# Mcu.net
KiCad netlist of a schematic drawn in Altium Designer
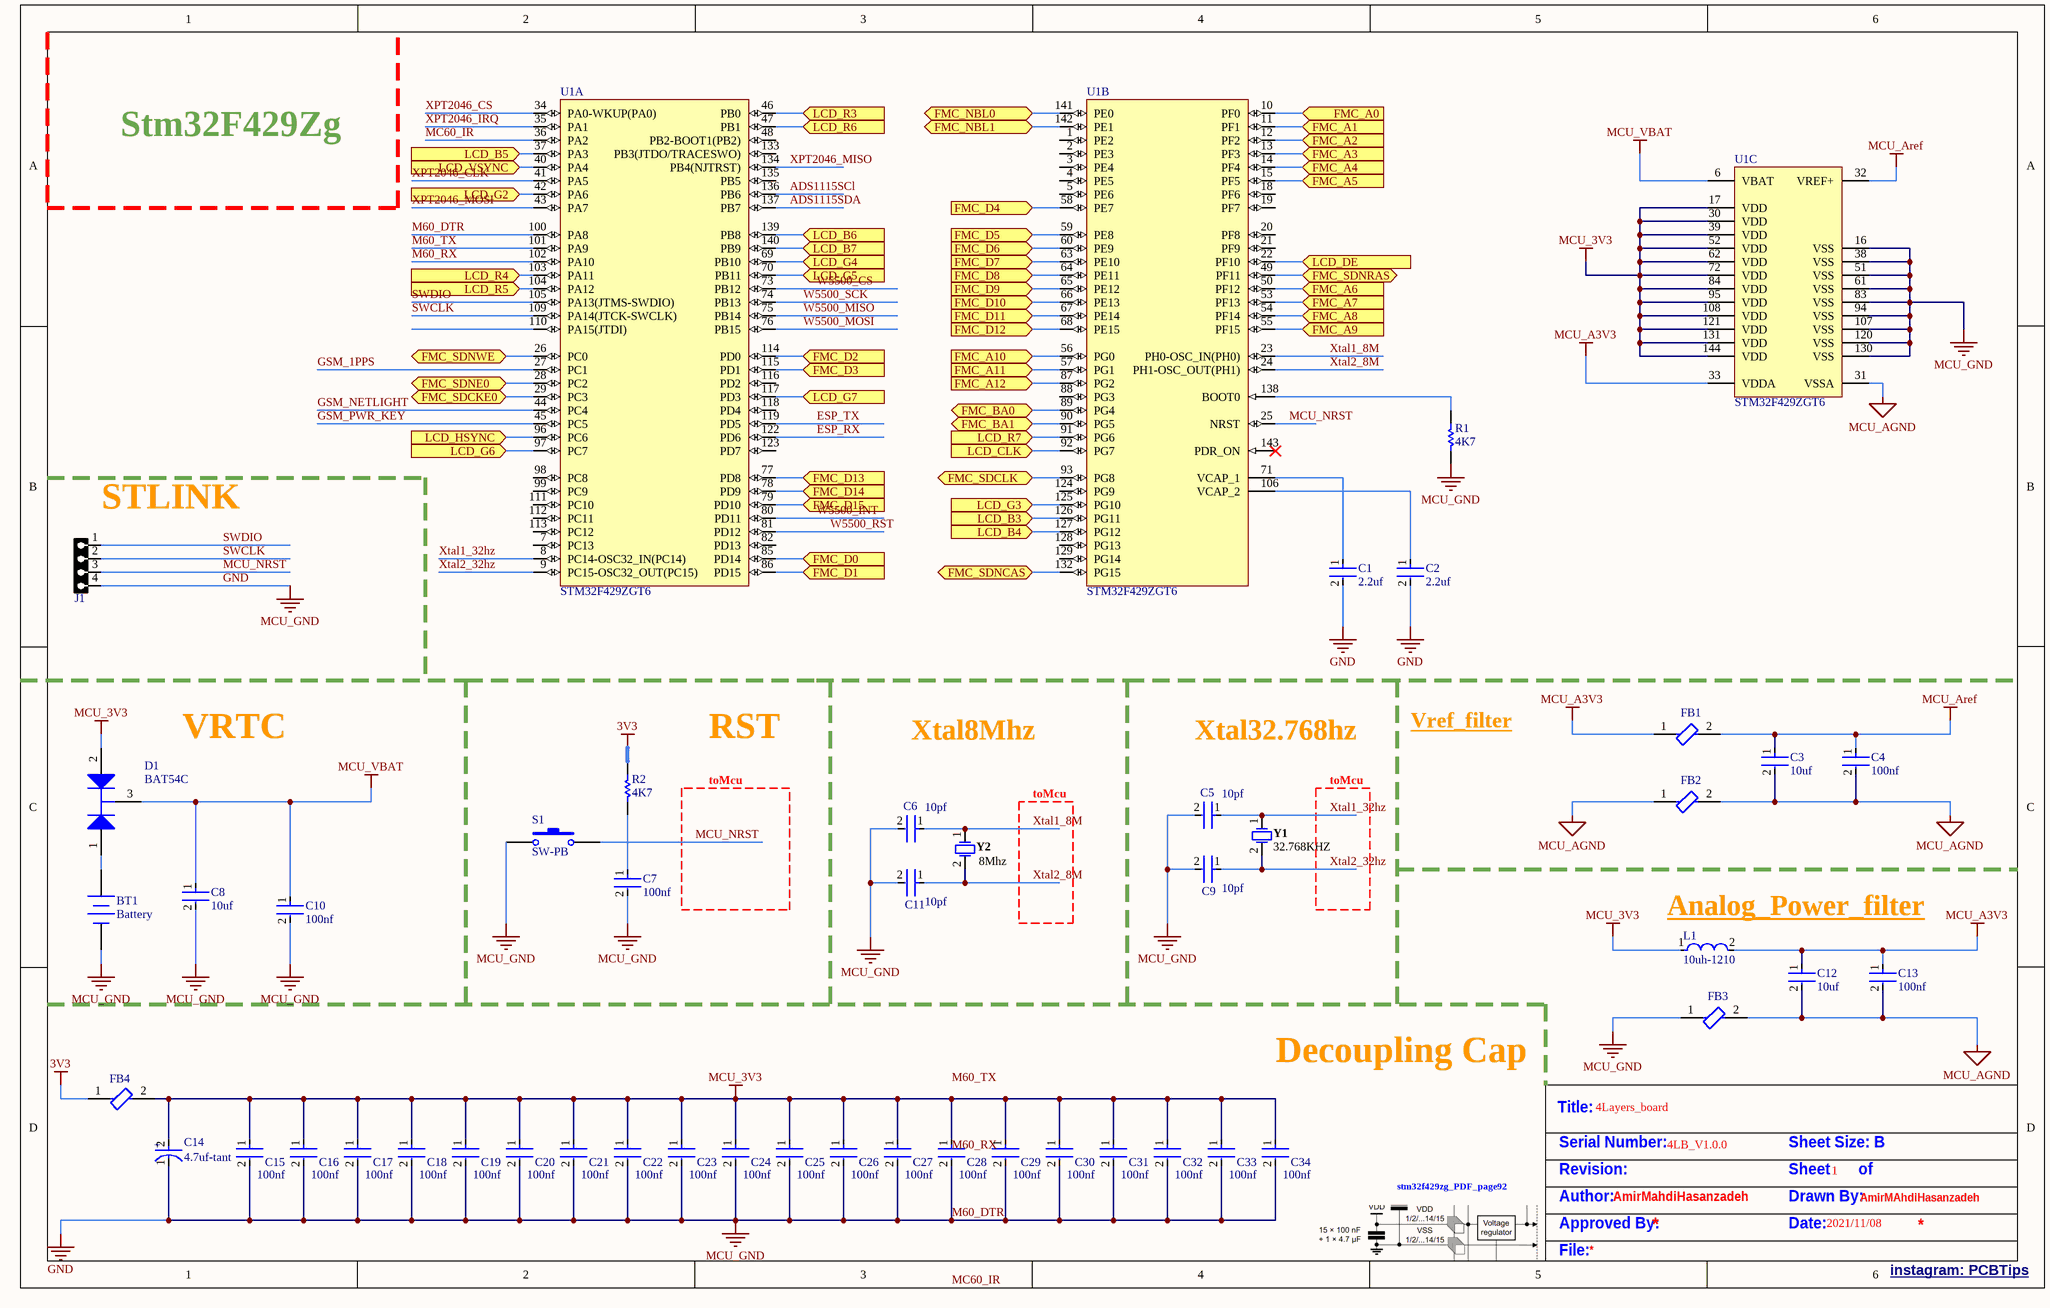
[diagram p0: Mcu.SchDoc]

(export (version "E")
  (design (tool "Eeschema 10.0.6"))
  (components
    (comp (ref "BT1")
      (value "Battery")
      (footprint "BTH1220")
      (description "Multicell Battery")
      (fields (field (name "PUBLISHER") "Altium Limited"))
      (libsource (lib "Miscellaneous Devices") (part "Battery"))
    )
    (comp (ref "C1")
      (value "2.2uf")
      (footprint "FP-C3216-160-0_2-IPC_A")
      (description "Multilayer Ceramic Capacitors 10uF ±10% 50V X5R SMD 1206")
      (fields (field (name "TOLERANCE") "10%") (field (name "VOLTAGE") "50V"))
      (libsource (lib "Altium Content Vault") (part "11868f565c42a9108669ba33697ecf6"))
    )
    (comp (ref "C2")
      (value "2.2uf")
      (footprint "FP-C3216-160-0_2-IPC_A")
      (description "Multilayer Ceramic Capacitors 10uF ±10% 50V X5R SMD 1206")
      (fields (field (name "TOLERANCE") "10%") (field (name "VOLTAGE") "50V"))
      (libsource (lib "Altium Content Vault") (part "11868f565c42a9108669ba33697ecf6"))
    )
    (comp (ref "C3")
      (value "10uf")
      (footprint "FP-C3216-160-0_2-IPC_A")
      (description "Multilayer Ceramic Capacitors 10uF ±10% 50V X5R SMD 1206")
      (fields (field (name "TOLERANCE") "10%") (field (name "VOLTAGE") "50V"))
      (libsource (lib "Altium Content Vault") (part "11868f565c42a9108669ba33697ecf6"))
    )
    (comp (ref "C4")
      (value "100nf")
      (footprint "FP-CGA3E-0_3-0_1-IPC_A")
      (description "Cap Ceramic 100nF 50V X7R 10% Pad SMD 0603 +125°C Automotive T/R")
      (fields (field (name "TOLERANCE") "10%") (field (name "VOLTAGE") "50V"))
      (libsource (lib "Altium Content Vault") (part "b4654b650e69147ec39a6b967a45e02"))
    )
    (comp (ref "C5")
      (value "10pf")
      (footprint "FP-CGA3E-0_3-0_1-IPC_A")
      (description "Cap Ceramic 100nF 50V X7R 10% Pad SMD 0603 +125°C Automotive T/R")
      (fields (field (name "TOLERANCE") "10%") (field (name "VOLTAGE") "50V"))
      (libsource (lib "Altium Content Vault") (part "b4654b650e69147ec39a6b967a45e02"))
    )
    (comp (ref "C6")
      (value "10pf")
      (footprint "FP-CGA3E-0_3-0_1-IPC_A")
      (description "Cap Ceramic 100nF 50V X7R 10% Pad SMD 0603 +125°C Automotive T/R")
      (fields (field (name "TOLERANCE") "10%") (field (name "VOLTAGE") "50V"))
      (libsource (lib "Altium Content Vault") (part "b4654b650e69147ec39a6b967a45e02"))
    )
    (comp (ref "C7")
      (value "100nf")
      (footprint "FP-CGA3E-0_3-0_1-IPC_A")
      (description "Cap Ceramic 100nF 50V X7R 10% Pad SMD 0603 +125°C Automotive T/R")
      (fields (field (name "TOLERANCE") "10%") (field (name "VOLTAGE") "50V"))
      (libsource (lib "Altium Content Vault") (part "b4654b650e69147ec39a6b967a45e02"))
    )
    (comp (ref "C8")
      (value "10uf")
      (footprint "FP-C3216-160-0_2-IPC_A")
      (description "Multilayer Ceramic Capacitors 10uF ±10% 50V X5R SMD 1206")
      (fields (field (name "TOLERANCE") "10%") (field (name "VOLTAGE") "50V"))
      (libsource (lib "Altium Content Vault") (part "11868f565c42a9108669ba33697ecf6"))
    )
    (comp (ref "C9")
      (value "10pf")
      (footprint "FP-CGA3E-0_3-0_1-IPC_A")
      (description "Cap Ceramic 100nF 50V X7R 10% Pad SMD 0603 +125°C Automotive T/R")
      (fields (field (name "TOLERANCE") "10%") (field (name "VOLTAGE") "50V"))
      (libsource (lib "Altium Content Vault") (part "b4654b650e69147ec39a6b967a45e02"))
    )
    (comp (ref "C10")
      (value "100nf")
      (footprint "FP-CGA3E-0_3-0_1-IPC_A")
      (description "Cap Ceramic 100nF 50V X7R 10% Pad SMD 0603 +125°C Automotive T/R")
      (fields (field (name "TOLERANCE") "10%") (field (name "VOLTAGE") "50V"))
      (libsource (lib "Altium Content Vault") (part "b4654b650e69147ec39a6b967a45e02"))
    )
    (comp (ref "C11")
      (value "10pf")
      (footprint "FP-CGA3E-0_3-0_1-IPC_A")
      (description "Cap Ceramic 100nF 50V X7R 10% Pad SMD 0603 +125°C Automotive T/R")
      (fields (field (name "TOLERANCE") "10%") (field (name "VOLTAGE") "50V"))
      (libsource (lib "Altium Content Vault") (part "b4654b650e69147ec39a6b967a45e02"))
    )
    (comp (ref "C12")
      (value "10uf")
      (footprint "FP-C3216-160-0_2-IPC_A")
      (description "Multilayer Ceramic Capacitors 10uF ±10% 50V X5R SMD 1206")
      (fields (field (name "TOLERANCE") "10%") (field (name "VOLTAGE") "50V"))
      (libsource (lib "Altium Content Vault") (part "11868f565c42a9108669ba33697ecf6"))
    )
    (comp (ref "C13")
      (value "100nf")
      (footprint "FP-CGA3E-0_3-0_1-IPC_A")
      (description "Cap Ceramic 100nF 50V X7R 10% Pad SMD 0603 +125°C Automotive T/R")
      (fields (field (name "TOLERANCE") "10%") (field (name "VOLTAGE") "50V"))
      (libsource (lib "Altium Content Vault") (part "b4654b650e69147ec39a6b967a45e02"))
    )
    (comp (ref "C14")
      (value "4.7uf-tant")
      (footprint "FP-T491A475K016AT-MFG")
      (description "CAP TANT 4.7UF 10% 16V 1206")
      (fields (field (name "TOLERANCE") "10%") (field (name "VOLTAGE") "16V"))
      (libsource (lib "Altium Content Vault") (part "cf48714ba7e38822c1575c7ec0b6d1f"))
    )
    (comp (ref "C15")
      (value "100nf")
      (footprint "FP-CGA3E-0_3-0_1-IPC_A")
      (description "Cap Ceramic 100nF 50V X7R 10% Pad SMD 0603 +125°C Automotive T/R")
      (fields (field (name "TOLERANCE") "10%") (field (name "VOLTAGE") "50V"))
      (libsource (lib "Altium Content Vault") (part "b4654b650e69147ec39a6b967a45e02"))
    )
    (comp (ref "C16")
      (value "100nf")
      (footprint "FP-CGA3E-0_3-0_1-IPC_A")
      (description "Cap Ceramic 100nF 50V X7R 10% Pad SMD 0603 +125°C Automotive T/R")
      (fields (field (name "TOLERANCE") "10%") (field (name "VOLTAGE") "50V"))
      (libsource (lib "Altium Content Vault") (part "b4654b650e69147ec39a6b967a45e02"))
    )
    (comp (ref "C17")
      (value "100nf")
      (footprint "FP-CGA3E-0_3-0_1-IPC_A")
      (description "Cap Ceramic 100nF 50V X7R 10% Pad SMD 0603 +125°C Automotive T/R")
      (fields (field (name "TOLERANCE") "10%") (field (name "VOLTAGE") "50V"))
      (libsource (lib "Altium Content Vault") (part "b4654b650e69147ec39a6b967a45e02"))
    )
    (comp (ref "C18")
      (value "100nf")
      (footprint "FP-CGA3E-0_3-0_1-IPC_A")
      (description "Cap Ceramic 100nF 50V X7R 10% Pad SMD 0603 +125°C Automotive T/R")
      (fields (field (name "TOLERANCE") "10%") (field (name "VOLTAGE") "50V"))
      (libsource (lib "Altium Content Vault") (part "b4654b650e69147ec39a6b967a45e02"))
    )
    (comp (ref "C19")
      (value "100nf")
      (footprint "FP-CGA3E-0_3-0_1-IPC_A")
      (description "Cap Ceramic 100nF 50V X7R 10% Pad SMD 0603 +125°C Automotive T/R")
      (fields (field (name "TOLERANCE") "10%") (field (name "VOLTAGE") "50V"))
      (libsource (lib "Altium Content Vault") (part "b4654b650e69147ec39a6b967a45e02"))
    )
    (comp (ref "C20")
      (value "100nf")
      (footprint "FP-CGA3E-0_3-0_1-IPC_A")
      (description "Cap Ceramic 100nF 50V X7R 10% Pad SMD 0603 +125°C Automotive T/R")
      (fields (field (name "TOLERANCE") "10%") (field (name "VOLTAGE") "50V"))
      (libsource (lib "Altium Content Vault") (part "b4654b650e69147ec39a6b967a45e02"))
    )
    (comp (ref "C21")
      (value "100nf")
      (footprint "FP-CGA3E-0_3-0_1-IPC_A")
      (description "Cap Ceramic 100nF 50V X7R 10% Pad SMD 0603 +125°C Automotive T/R")
      (fields (field (name "TOLERANCE") "10%") (field (name "VOLTAGE") "50V"))
      (libsource (lib "Altium Content Vault") (part "b4654b650e69147ec39a6b967a45e02"))
    )
    (comp (ref "C22")
      (value "100nf")
      (footprint "FP-CGA3E-0_3-0_1-IPC_A")
      (description "Cap Ceramic 100nF 50V X7R 10% Pad SMD 0603 +125°C Automotive T/R")
      (fields (field (name "TOLERANCE") "10%") (field (name "VOLTAGE") "50V"))
      (libsource (lib "Altium Content Vault") (part "b4654b650e69147ec39a6b967a45e02"))
    )
    (comp (ref "C23")
      (value "100nf")
      (footprint "FP-CGA3E-0_3-0_1-IPC_A")
      (description "Cap Ceramic 100nF 50V X7R 10% Pad SMD 0603 +125°C Automotive T/R")
      (fields (field (name "TOLERANCE") "10%") (field (name "VOLTAGE") "50V"))
      (libsource (lib "Altium Content Vault") (part "b4654b650e69147ec39a6b967a45e02"))
    )
    (comp (ref "C24")
      (value "100nf")
      (footprint "FP-CGA3E-0_3-0_1-IPC_A")
      (description "Cap Ceramic 100nF 50V X7R 10% Pad SMD 0603 +125°C Automotive T/R")
      (fields (field (name "TOLERANCE") "10%") (field (name "VOLTAGE") "50V"))
      (libsource (lib "Altium Content Vault") (part "b4654b650e69147ec39a6b967a45e02"))
    )
    (comp (ref "C25")
      (value "100nf")
      (footprint "FP-CGA3E-0_3-0_1-IPC_A")
      (description "Cap Ceramic 100nF 50V X7R 10% Pad SMD 0603 +125°C Automotive T/R")
      (fields (field (name "TOLERANCE") "10%") (field (name "VOLTAGE") "50V"))
      (libsource (lib "Altium Content Vault") (part "b4654b650e69147ec39a6b967a45e02"))
    )
    (comp (ref "C26")
      (value "100nf")
      (footprint "FP-CGA3E-0_3-0_1-IPC_A")
      (description "Cap Ceramic 100nF 50V X7R 10% Pad SMD 0603 +125°C Automotive T/R")
      (fields (field (name "TOLERANCE") "10%") (field (name "VOLTAGE") "50V"))
      (libsource (lib "Altium Content Vault") (part "b4654b650e69147ec39a6b967a45e02"))
    )
    (comp (ref "C27")
      (value "100nf")
      (footprint "FP-CGA3E-0_3-0_1-IPC_A")
      (description "Cap Ceramic 100nF 50V X7R 10% Pad SMD 0603 +125°C Automotive T/R")
      (fields (field (name "TOLERANCE") "10%") (field (name "VOLTAGE") "50V"))
      (libsource (lib "Altium Content Vault") (part "b4654b650e69147ec39a6b967a45e02"))
    )
    (comp (ref "C28")
      (value "100nf")
      (footprint "FP-CGA3E-0_3-0_1-IPC_A")
      (description "Cap Ceramic 100nF 50V X7R 10% Pad SMD 0603 +125°C Automotive T/R")
      (fields (field (name "TOLERANCE") "10%") (field (name "VOLTAGE") "50V"))
      (libsource (lib "Altium Content Vault") (part "b4654b650e69147ec39a6b967a45e02"))
    )
    (comp (ref "C29")
      (value "100nf")
      (footprint "FP-CGA3E-0_3-0_1-IPC_A")
      (description "Cap Ceramic 100nF 50V X7R 10% Pad SMD 0603 +125°C Automotive T/R")
      (fields (field (name "TOLERANCE") "10%") (field (name "VOLTAGE") "50V"))
      (libsource (lib "Altium Content Vault") (part "b4654b650e69147ec39a6b967a45e02"))
    )
    (comp (ref "C30")
      (value "100nf")
      (footprint "FP-CGA3E-0_3-0_1-IPC_A")
      (description "Cap Ceramic 100nF 50V X7R 10% Pad SMD 0603 +125°C Automotive T/R")
      (fields (field (name "TOLERANCE") "10%") (field (name "VOLTAGE") "50V"))
      (libsource (lib "Altium Content Vault") (part "b4654b650e69147ec39a6b967a45e02"))
    )
    (comp (ref "C31")
      (value "100nf")
      (footprint "FP-CGA3E-0_3-0_1-IPC_A")
      (description "Cap Ceramic 100nF 50V X7R 10% Pad SMD 0603 +125°C Automotive T/R")
      (fields (field (name "TOLERANCE") "10%") (field (name "VOLTAGE") "50V"))
      (libsource (lib "Altium Content Vault") (part "b4654b650e69147ec39a6b967a45e02"))
    )
    (comp (ref "C32")
      (value "100nf")
      (footprint "FP-CGA3E-0_3-0_1-IPC_A")
      (description "Cap Ceramic 100nF 50V X7R 10% Pad SMD 0603 +125°C Automotive T/R")
      (fields (field (name "TOLERANCE") "10%") (field (name "VOLTAGE") "50V"))
      (libsource (lib "Altium Content Vault") (part "b4654b650e69147ec39a6b967a45e02"))
    )
    (comp (ref "C33")
      (value "100nf")
      (footprint "FP-CGA3E-0_3-0_1-IPC_A")
      (description "Cap Ceramic 100nF 50V X7R 10% Pad SMD 0603 +125°C Automotive T/R")
      (fields (field (name "TOLERANCE") "10%") (field (name "VOLTAGE") "50V"))
      (libsource (lib "Altium Content Vault") (part "b4654b650e69147ec39a6b967a45e02"))
    )
    (comp (ref "C34")
      (value "100nf")
      (footprint "FP-CGA3E-0_3-0_1-IPC_A")
      (description "Cap Ceramic 100nF 50V X7R 10% Pad SMD 0603 +125°C Automotive T/R")
      (fields (field (name "TOLERANCE") "10%") (field (name "VOLTAGE") "50V"))
      (libsource (lib "Altium Content Vault") (part "b4654b650e69147ec39a6b967a45e02"))
    )
    (comp (ref "D1")
      (value "BAT54C")
      (footprint "ONSC-SOT-323-3-419-04_V")
      (description "Dual Series Cathode Schottky Barrier Diodes, 3-Pin SOT-323, Pb-Free, Tape and Reel")
      (fields (field (name "MANUFACTURER") "On Semiconductor") (field (name "PARTNUMBER") "SBAT54CWT1G"))
      (libsource (lib "Altium Content Vault") (part "ONSC-D-A1A2K3-3"))
    )
    (comp (ref "FB1")
      (value "MMZ1608R600ATA00")
      (footprint "FP-MMZ1608-0_8-MFG")
      (description "Signal Line Ferrite Bead 60Ω  @ 100MHz 800mA DCR 100mΩ SMD 0603")
      (fields (field (name "TOLERANCE") "25%"))
      (libsource (lib "Altium Content Vault") (part "5f30dd21d616792df468990f7003faa"))
    )
    (comp (ref "FB2")
      (value "MMZ1608R600ATA00")
      (footprint "FP-MMZ1608-0_8-MFG")
      (description "Signal Line Ferrite Bead 60Ω  @ 100MHz 800mA DCR 100mΩ SMD 0603")
      (fields (field (name "TOLERANCE") "25%"))
      (libsource (lib "Altium Content Vault") (part "5f30dd21d616792df468990f7003faa"))
    )
    (comp (ref "FB3")
      (value "MMZ1608R600ATA00")
      (footprint "FP-MMZ1608-0_8-MFG")
      (description "Signal Line Ferrite Bead 60Ω  @ 100MHz 800mA DCR 100mΩ SMD 0603")
      (fields (field (name "TOLERANCE") "25%"))
      (libsource (lib "Altium Content Vault") (part "5f30dd21d616792df468990f7003faa"))
    )
    (comp (ref "FB4")
      (value "MMZ1608R600ATA00")
      (footprint "FP-MMZ1608-0_8-MFG")
      (description "Signal Line Ferrite Bead 60Ω  @ 100MHz 800mA DCR 100mΩ SMD 0603")
      (fields (field (name "TOLERANCE") "25%"))
      (libsource (lib "Altium Content Vault") (part "5f30dd21d616792df468990f7003faa"))
    )
    (comp (ref "J1")
      (value "HDRF4")
      (footprint "HDR_F_1X4")
      (description "CONN, HEADER, Female, pitch: 2.54mm, 4POS")
      (libsource (lib "conn_header_2.54_st") (part "HDR_F_1X4"))
    )
    (comp (ref "L1")
      (value "10uh-1210")
      (footprint "FP-CB3225-IPC_A")
      (description "SMD Inductors 10uH ±20% 0.9A 0.1729Ω 1210")
      (fields (field (name "TOLERANCE") "20%"))
      (libsource (lib "Altium Content Vault") (part "725321dda6339637d4d059423bc1c3c"))
    )
    (comp (ref "R1")
      (value "4K7")
      (footprint "RESC1608X55X25ML10T15")
      (description "Chip Resistor, 0 Ohm, +/- 5%, 0.1 W, -55 to 155 degC, 0603 (1608 Metric), RoHS, Tape and Reel")
      (fields (field (name "TOLERANCE") "5%") (field (name "MANUFACTURER") "Yageo"))
      (libsource (lib "Altium Content Vault") (part "RES-2"))
    )
    (comp (ref "R2")
      (value "4K7")
      (footprint "RESC1608X55X25ML10T15")
      (description "Chip Resistor, 0 Ohm, +/- 5%, 0.1 W, -55 to 155 degC, 0603 (1608 Metric), RoHS, Tape and Reel")
      (fields (field (name "TOLERANCE") "5%") (field (name "MANUFACTURER") "Yageo"))
      (libsource (lib "Altium Content Vault") (part "RES-2"))
    )
    (comp (ref "S1")
      (value "SW-PB")
      (footprint "SWPBS_SPST_6X3X5")
      (description "Switch")
      (fields (field (name "PUBLISHER") "Altium Limited"))
      (libsource (lib "Miscellaneous Devices") (part "SW-PB"))
    )
    (comp (ref "U1")
      (value "STM32F429ZGT6")
      (footprint "STM-LQFP144_V")
      (fields (field (name "MANUFACTURER") "STMicroelectronics"))
      (libsource (lib "Altium Content Vault") (part "MC-ARM-STM32F4X9-SQ144"))
    )
    (comp (ref "Y1")
      (value "32.768KHZ")
      (footprint "ABRA-AB26T")
      (description "Crystal, 12.5 pF, 32.768 KHz, -10 to 60 degC, 2-Pin THD, RoHS, Bulk")
      (fields (field (name "MANUFACTURER") "ABRACON") (field (name "TOLERANCE") "20PPM"))
      (libsource (lib "Altium Content Vault") (part "XTAL-1-2-2"))
    )
    (comp (ref "Y2")
      (value "8Mhz")
      (footprint "FOX-HC49SDLF_V")
      (description "Resistance Weld Crystal, 8 MHz, +/- 30 ppm, -20 to 70 degC, 2-Pin SMD, RoHS, Tape and Reel")
      (fields (field (name "MANUFACTURER") "FOX Electronics") (field (name "TOLERANCE") "50ppm"))
      (libsource (lib "Altium Content Vault") (part "XTAL-1-2-2"))
    )
  )
  (nets
    (net (code "1") (name "/ADS1115SCl") (class "Default")
      (node (ref "U1") (pin "136") (pinfunction "PB6_136") (pintype "bidirectional"))
    )
    (net (code "2") (name "/ADS1115SDA") (class "Default")
      (node (ref "U1") (pin "137") (pinfunction "PB7_137") (pintype "bidirectional"))
    )
    (net (code "3") (name "/ESP_RX") (class "Default")
      (node (ref "U1") (pin "122") (pinfunction "PD6_122") (pintype "bidirectional"))
    )
    (net (code "4") (name "/ESP_TX") (class "Default")
      (node (ref "U1") (pin "119") (pinfunction "PD5_119") (pintype "bidirectional"))
    )
    (net (code "5") (name "/FMC_A0") (class "Default")
      (node (ref "U1") (pin "10") (pinfunction "PF0_10") (pintype "bidirectional"))
    )
    (net (code "6") (name "/FMC_A1") (class "Default")
      (node (ref "U1") (pin "11") (pinfunction "PF1_11") (pintype "bidirectional"))
    )
    (net (code "7") (name "/FMC_A2") (class "Default")
      (node (ref "U1") (pin "12") (pinfunction "PF2_12") (pintype "bidirectional"))
    )
    (net (code "8") (name "/FMC_A3") (class "Default")
      (node (ref "U1") (pin "13") (pinfunction "PF3_13") (pintype "bidirectional"))
    )
    (net (code "9") (name "/FMC_A4") (class "Default")
      (node (ref "U1") (pin "14") (pinfunction "PF4_14") (pintype "bidirectional"))
    )
    (net (code "10") (name "/FMC_A5") (class "Default")
      (node (ref "U1") (pin "15") (pinfunction "PF5_15") (pintype "bidirectional"))
    )
    (net (code "11") (name "/FMC_A6") (class "Default")
      (node (ref "U1") (pin "50") (pinfunction "PF12_50") (pintype "bidirectional"))
    )
    (net (code "12") (name "/FMC_A7") (class "Default")
      (node (ref "U1") (pin "53") (pinfunction "PF13_53") (pintype "bidirectional"))
    )
    (net (code "13") (name "/FMC_A8") (class "Default")
      (node (ref "U1") (pin "54") (pinfunction "PF14_54") (pintype "bidirectional"))
    )
    (net (code "14") (name "/FMC_A9") (class "Default")
      (node (ref "U1") (pin "55") (pinfunction "PF15_55") (pintype "bidirectional"))
    )
    (net (code "15") (name "/FMC_A10") (class "Default")
      (node (ref "U1") (pin "56") (pinfunction "PG0_56") (pintype "bidirectional"))
    )
    (net (code "16") (name "/FMC_A11") (class "Default")
      (node (ref "U1") (pin "57") (pinfunction "PG1_57") (pintype "bidirectional"))
    )
    (net (code "17") (name "/FMC_A12") (class "Default")
      (node (ref "U1") (pin "87") (pinfunction "PG2_87") (pintype "bidirectional"))
    )
    (net (code "18") (name "/FMC_BA0") (class "Default")
      (node (ref "U1") (pin "89") (pinfunction "PG4_89") (pintype "bidirectional"))
    )
    (net (code "19") (name "/FMC_BA1") (class "Default")
      (node (ref "U1") (pin "90") (pinfunction "PG5_90") (pintype "bidirectional"))
    )
    (net (code "20") (name "/FMC_D0") (class "Default")
      (node (ref "U1") (pin "85") (pinfunction "PD14_85") (pintype "bidirectional"))
    )
    (net (code "21") (name "/FMC_D1") (class "Default")
      (node (ref "U1") (pin "86") (pinfunction "PD15_86") (pintype "bidirectional"))
    )
    (net (code "22") (name "/FMC_D2") (class "Default")
      (node (ref "U1") (pin "114") (pinfunction "PD0_114") (pintype "bidirectional"))
    )
    (net (code "23") (name "/FMC_D3") (class "Default")
      (node (ref "U1") (pin "115") (pinfunction "PD1_115") (pintype "bidirectional"))
    )
    (net (code "24") (name "/FMC_D4") (class "Default")
      (node (ref "U1") (pin "58") (pinfunction "PE7_58") (pintype "bidirectional"))
    )
    (net (code "25") (name "/FMC_D5") (class "Default")
      (node (ref "U1") (pin "59") (pinfunction "PE8_59") (pintype "bidirectional"))
    )
    (net (code "26") (name "/FMC_D6") (class "Default")
      (node (ref "U1") (pin "60") (pinfunction "PE9_60") (pintype "bidirectional"))
    )
    (net (code "27") (name "/FMC_D7") (class "Default")
      (node (ref "U1") (pin "63") (pinfunction "PE10_63") (pintype "bidirectional"))
    )
    (net (code "28") (name "/FMC_D8") (class "Default")
      (node (ref "U1") (pin "64") (pinfunction "PE11_64") (pintype "bidirectional"))
    )
    (net (code "29") (name "/FMC_D9") (class "Default")
      (node (ref "U1") (pin "65") (pinfunction "PE12_65") (pintype "bidirectional"))
    )
    (net (code "30") (name "/FMC_D10") (class "Default")
      (node (ref "U1") (pin "66") (pinfunction "PE13_66") (pintype "bidirectional"))
    )
    (net (code "31") (name "/FMC_D11") (class "Default")
      (node (ref "U1") (pin "67") (pinfunction "PE14_67") (pintype "bidirectional"))
    )
    (net (code "32") (name "/FMC_D12") (class "Default")
      (node (ref "U1") (pin "68") (pinfunction "PE15_68") (pintype "bidirectional"))
    )
    (net (code "33") (name "/FMC_D13") (class "Default")
      (node (ref "U1") (pin "77") (pinfunction "PD8_77") (pintype "bidirectional"))
    )
    (net (code "34") (name "/FMC_D14") (class "Default")
      (node (ref "U1") (pin "78") (pinfunction "PD9_78") (pintype "bidirectional"))
    )
    (net (code "35") (name "/FMC_D15") (class "Default")
      (node (ref "U1") (pin "79") (pinfunction "PD10_79") (pintype "bidirectional"))
    )
    (net (code "36") (name "/FMC_NBL0") (class "Default")
      (node (ref "U1") (pin "141") (pinfunction "PE0_141") (pintype "bidirectional"))
    )
    (net (code "37") (name "/FMC_NBL1") (class "Default")
      (node (ref "U1") (pin "142") (pinfunction "PE1_142") (pintype "bidirectional"))
    )
    (net (code "38") (name "/FMC_SDCKE0") (class "Default")
      (node (ref "U1") (pin "29") (pinfunction "PC3_29") (pintype "bidirectional"))
    )
    (net (code "39") (name "/FMC_SDCLK") (class "Default")
      (node (ref "U1") (pin "93") (pinfunction "PG8_93") (pintype "bidirectional"))
    )
    (net (code "40") (name "/FMC_SDNCAS") (class "Default")
      (node (ref "U1") (pin "132") (pinfunction "PG15_132") (pintype "bidirectional"))
    )
    (net (code "41") (name "/FMC_SDNE0") (class "Default")
      (node (ref "U1") (pin "28") (pinfunction "PC2_28") (pintype "bidirectional"))
    )
    (net (code "42") (name "/FMC_SDNRAS") (class "Default")
      (node (ref "U1") (pin "49") (pinfunction "PF11_49") (pintype "bidirectional"))
    )
    (net (code "43") (name "/FMC_SDNWE") (class "Default")
      (node (ref "U1") (pin "26") (pinfunction "PC0_26") (pintype "bidirectional"))
    )
    (net (code "44") (name "/GSM_1PPS") (class "Default")
      (node (ref "U1") (pin "27") (pinfunction "PC1_27") (pintype "bidirectional"))
    )
    (net (code "45") (name "/GSM_NETLIGHT") (class "Default")
      (node (ref "U1") (pin "44") (pinfunction "PC4_44") (pintype "bidirectional"))
    )
    (net (code "46") (name "/GSM_PWR_KEY") (class "Default")
      (node (ref "U1") (pin "45") (pinfunction "PC5_45") (pintype "bidirectional"))
    )
    (net (code "47") (name "/LCD_B3") (class "Default")
      (node (ref "U1") (pin "126") (pinfunction "PG11_126") (pintype "bidirectional"))
    )
    (net (code "48") (name "/LCD_B4") (class "Default")
      (node (ref "U1") (pin "127") (pinfunction "PG12_127") (pintype "bidirectional"))
    )
    (net (code "49") (name "/LCD_B5") (class "Default")
      (node (ref "U1") (pin "37") (pinfunction "PA3_37") (pintype "bidirectional"))
    )
    (net (code "50") (name "/LCD_B6") (class "Default")
      (node (ref "U1") (pin "139") (pinfunction "PB8_139") (pintype "bidirectional"))
    )
    (net (code "51") (name "/LCD_B7") (class "Default")
      (node (ref "U1") (pin "140") (pinfunction "PB9_140") (pintype "bidirectional"))
    )
    (net (code "52") (name "/LCD_CLK") (class "Default")
      (node (ref "U1") (pin "92") (pinfunction "PG7_92") (pintype "bidirectional"))
    )
    (net (code "53") (name "/LCD_DE") (class "Default")
      (node (ref "U1") (pin "22") (pinfunction "PF10_22") (pintype "bidirectional"))
    )
    (net (code "54") (name "/LCD_G2") (class "Default")
      (node (ref "U1") (pin "42") (pinfunction "PA6_42") (pintype "bidirectional"))
    )
    (net (code "55") (name "/LCD_G3") (class "Default")
      (node (ref "U1") (pin "125") (pinfunction "PG10_125") (pintype "bidirectional"))
    )
    (net (code "56") (name "/LCD_G4") (class "Default")
      (node (ref "U1") (pin "69") (pinfunction "PB10_69") (pintype "bidirectional"))
    )
    (net (code "57") (name "/LCD_G5") (class "Default")
      (node (ref "U1") (pin "70") (pinfunction "PB11_70") (pintype "bidirectional"))
    )
    (net (code "58") (name "/LCD_G6") (class "Default")
      (node (ref "U1") (pin "97") (pinfunction "PC7_97") (pintype "bidirectional"))
    )
    (net (code "59") (name "/LCD_G7") (class "Default")
      (node (ref "U1") (pin "117") (pinfunction "PD3_117") (pintype "bidirectional"))
    )
    (net (code "60") (name "/LCD_HSYNC") (class "Default")
      (node (ref "U1") (pin "96") (pinfunction "PC6_96") (pintype "bidirectional"))
    )
    (net (code "61") (name "/LCD_R3") (class "Default")
      (node (ref "U1") (pin "46") (pinfunction "PB0_46") (pintype "bidirectional"))
    )
    (net (code "62") (name "/LCD_R4") (class "Default")
      (node (ref "U1") (pin "103") (pinfunction "PA11_103") (pintype "bidirectional"))
    )
    (net (code "63") (name "/LCD_R5") (class "Default")
      (node (ref "U1") (pin "104") (pinfunction "PA12_104") (pintype "bidirectional"))
    )
    (net (code "64") (name "/LCD_R6") (class "Default")
      (node (ref "U1") (pin "47") (pinfunction "PB1_47") (pintype "bidirectional"))
    )
    (net (code "65") (name "/LCD_R7") (class "Default")
      (node (ref "U1") (pin "91") (pinfunction "PG6_91") (pintype "bidirectional"))
    )
    (net (code "66") (name "/LCD_VSYNC") (class "Default")
      (node (ref "U1") (pin "40") (pinfunction "PA4_40") (pintype "bidirectional"))
    )
    (net (code "67") (name "/M60_RX") (class "Default")
      (node (ref "U1") (pin "102") (pinfunction "PA10_102") (pintype "bidirectional"))
    )
    (net (code "68") (name "/M60_TX") (class "Default")
      (node (ref "U1") (pin "101") (pinfunction "PA9_101") (pintype "bidirectional"))
    )
    (net (code "69") (name "/MC60_IR") (class "Default")
      (node (ref "U1") (pin "36") (pinfunction "PA2_36") (pintype "bidirectional"))
    )
    (net (code "70") (name "/MCU_NRST") (class "Default")
      (node (ref "J1") (pin "3") (pinfunction "3_3") (pintype "passive"))
      (node (ref "S1") (pin "1") (pinfunction "1_1") (pintype "passive"))
      (node (ref "U1") (pin "25") (pinfunction "NRST_25") (pintype "bidirectional"))
    )
    (net (code "71") (name "/SWCLK") (class "Default")
      (node (ref "J1") (pin "2") (pinfunction "2_2") (pintype "passive"))
      (node (ref "U1") (pin "109") (pinfunction "PA14(JTCK-SWCLK)_109") (pintype "bidirectional"))
    )
    (net (code "72") (name "/SWDIO") (class "Default")
      (node (ref "J1") (pin "1") (pinfunction "1_1") (pintype "passive"))
      (node (ref "U1") (pin "105") (pinfunction "PA13(JTMS-SWDIO)_105") (pintype "bidirectional"))
    )
    (net (code "73") (name "/W5500_CS") (class "Default")
      (node (ref "U1") (pin "73") (pinfunction "PB12_73") (pintype "bidirectional"))
    )
    (net (code "74") (name "/W5500_INT") (class "Default")
      (node (ref "U1") (pin "80") (pinfunction "PD11_80") (pintype "bidirectional"))
    )
    (net (code "75") (name "/W5500_MISO") (class "Default")
      (node (ref "U1") (pin "75") (pinfunction "PB14_75") (pintype "bidirectional"))
    )
    (net (code "76") (name "/W5500_MOSI") (class "Default")
      (node (ref "U1") (pin "76") (pinfunction "PB15_76") (pintype "bidirectional"))
    )
    (net (code "77") (name "/W5500_RST") (class "Default")
      (node (ref "U1") (pin "81") (pinfunction "PD12_81") (pintype "bidirectional"))
    )
    (net (code "78") (name "/W5500_SCK") (class "Default")
      (node (ref "U1") (pin "74") (pinfunction "PB13_74") (pintype "bidirectional"))
    )
    (net (code "79") (name "/XPT2046_CLK") (class "Default")
      (node (ref "U1") (pin "41") (pinfunction "PA5_41") (pintype "bidirectional"))
    )
    (net (code "80") (name "/XPT2046_CS") (class "Default")
      (node (ref "U1") (pin "34") (pinfunction "PA0-WKUP(PA0)_34") (pintype "bidirectional"))
    )
    (net (code "81") (name "/XPT2046_IRQ") (class "Default")
      (node (ref "U1") (pin "35") (pinfunction "PA1_35") (pintype "bidirectional"))
    )
    (net (code "82") (name "/XPT2046_MISO") (class "Default")
      (node (ref "U1") (pin "134") (pinfunction "PB4(NJTRST)_134") (pintype "bidirectional"))
    )
    (net (code "83") (name "/XPT2046_MOSI") (class "Default")
      (node (ref "U1") (pin "43") (pinfunction "PA7_43") (pintype "bidirectional"))
    )
    (net (code "84") (name "/Xtal1_8M") (class "Default")
      (node (ref "C6") (pin "1") (pinfunction "1_1") (pintype "passive"))
      (node (ref "U1") (pin "23") (pinfunction "PH0-OSC_IN(PH0)_23") (pintype "bidirectional"))
      (node (ref "Y2") (pin "1") (pinfunction "1_1") (pintype "passive"))
    )
    (net (code "85") (name "/Xtal1_32hz") (class "Default")
      (node (ref "C5") (pin "1") (pinfunction "1_1") (pintype "passive"))
      (node (ref "U1") (pin "8") (pinfunction "PC14-OSC32_IN(PC14)_8") (pintype "bidirectional"))
      (node (ref "Y1") (pin "1") (pinfunction "1_1") (pintype "passive"))
    )
    (net (code "86") (name "/Xtal2_8M") (class "Default")
      (node (ref "C11") (pin "1") (pinfunction "1_1") (pintype "passive"))
      (node (ref "U1") (pin "24") (pinfunction "PH1-OSC_OUT(PH1)_24") (pintype "bidirectional"))
      (node (ref "Y2") (pin "2") (pinfunction "2_2") (pintype "passive"))
    )
    (net (code "87") (name "/Xtal2_32hz") (class "Default")
      (node (ref "C9") (pin "1") (pinfunction "1_1") (pintype "passive"))
      (node (ref "U1") (pin "9") (pinfunction "PC15-OSC32_OUT(PC15)_9") (pintype "bidirectional"))
      (node (ref "Y1") (pin "2") (pinfunction "2_2") (pintype "passive"))
    )
    (net (code "88") (name "3V3") (class "Default")
      (node (ref "FB4") (pin "1") (pinfunction "1_1") (pintype "passive"))
      (node (ref "R2") (pin "2") (pinfunction "2_2") (pintype "passive"))
    )
    (net (code "89") (name "GND") (class "Default")
      (node (ref "BT1") (pin "2") (pinfunction "-_2") (pintype "passive"))
      (node (ref "C1") (pin "2") (pinfunction "2_2") (pintype "passive"))
      (node (ref "C10") (pin "2") (pinfunction "2_2") (pintype "passive"))
      (node (ref "C11") (pin "2") (pinfunction "2_2") (pintype "passive"))
      (node (ref "C14") (pin "1") (pinfunction "C_1") (pintype "passive"))
      (node (ref "C15") (pin "2") (pinfunction "2_2") (pintype "passive"))
      (node (ref "C16") (pin "2") (pinfunction "2_2") (pintype "passive"))
      (node (ref "C17") (pin "2") (pinfunction "2_2") (pintype "passive"))
      (node (ref "C18") (pin "2") (pinfunction "2_2") (pintype "passive"))
      (node (ref "C19") (pin "2") (pinfunction "2_2") (pintype "passive"))
      (node (ref "C2") (pin "2") (pinfunction "2_2") (pintype "passive"))
      (node (ref "C20") (pin "2") (pinfunction "2_2") (pintype "passive"))
      (node (ref "C21") (pin "2") (pinfunction "2_2") (pintype "passive"))
      (node (ref "C22") (pin "2") (pinfunction "2_2") (pintype "passive"))
      (node (ref "C23") (pin "2") (pinfunction "2_2") (pintype "passive"))
      (node (ref "C24") (pin "2") (pinfunction "2_2") (pintype "passive"))
      (node (ref "C25") (pin "2") (pinfunction "2_2") (pintype "passive"))
      (node (ref "C26") (pin "2") (pinfunction "2_2") (pintype "passive"))
      (node (ref "C27") (pin "2") (pinfunction "2_2") (pintype "passive"))
      (node (ref "C28") (pin "2") (pinfunction "2_2") (pintype "passive"))
      (node (ref "C29") (pin "2") (pinfunction "2_2") (pintype "passive"))
      (node (ref "C30") (pin "2") (pinfunction "2_2") (pintype "passive"))
      (node (ref "C31") (pin "2") (pinfunction "2_2") (pintype "passive"))
      (node (ref "C32") (pin "2") (pinfunction "2_2") (pintype "passive"))
      (node (ref "C33") (pin "2") (pinfunction "2_2") (pintype "passive"))
      (node (ref "C34") (pin "2") (pinfunction "2_2") (pintype "passive"))
      (node (ref "C5") (pin "2") (pinfunction "2_2") (pintype "passive"))
      (node (ref "C6") (pin "2") (pinfunction "2_2") (pintype "passive"))
      (node (ref "C7") (pin "2") (pinfunction "2_2") (pintype "passive"))
      (node (ref "C8") (pin "2") (pinfunction "2_2") (pintype "passive"))
      (node (ref "C9") (pin "2") (pinfunction "2_2") (pintype "passive"))
      (node (ref "FB3") (pin "1") (pinfunction "1_1") (pintype "passive"))
      (node (ref "J1") (pin "4") (pinfunction "4_4") (pintype "passive"))
      (node (ref "R1") (pin "1") (pinfunction "1_1") (pintype "passive"))
      (node (ref "S1") (pin "2") (pinfunction "2_2") (pintype "passive"))
      (node (ref "U1") (pin "100") (pinfunction "PA8_100") (pintype "bidirectional"))
      (node (ref "U1") (pin "107") (pinfunction "VSS_107") (pintype "power_in"))
      (node (ref "U1") (pin "120") (pinfunction "VSS_120") (pintype "power_in"))
      (node (ref "U1") (pin "130") (pinfunction "VSS_130") (pintype "power_in"))
      (node (ref "U1") (pin "16") (pinfunction "VSS_16") (pintype "power_in"))
      (node (ref "U1") (pin "38") (pinfunction "VSS_38") (pintype "power_in"))
      (node (ref "U1") (pin "51") (pinfunction "VSS_51") (pintype "power_in"))
      (node (ref "U1") (pin "61") (pinfunction "VSS_61") (pintype "power_in"))
      (node (ref "U1") (pin "83") (pinfunction "VSS_83") (pintype "power_in"))
      (node (ref "U1") (pin "94") (pinfunction "VSS_94") (pintype "power_in"))
    )
    (net (code "90") (name "MCU_3V3") (class "Default")
      (node (ref "C14") (pin "2") (pinfunction "A_2") (pintype "passive"))
      (node (ref "C15") (pin "1") (pinfunction "1_1") (pintype "passive"))
      (node (ref "C16") (pin "1") (pinfunction "1_1") (pintype "passive"))
      (node (ref "C17") (pin "1") (pinfunction "1_1") (pintype "passive"))
      (node (ref "C18") (pin "1") (pinfunction "1_1") (pintype "passive"))
      (node (ref "C19") (pin "1") (pinfunction "1_1") (pintype "passive"))
      (node (ref "C20") (pin "1") (pinfunction "1_1") (pintype "passive"))
      (node (ref "C21") (pin "1") (pinfunction "1_1") (pintype "passive"))
      (node (ref "C22") (pin "1") (pinfunction "1_1") (pintype "passive"))
      (node (ref "C23") (pin "1") (pinfunction "1_1") (pintype "passive"))
      (node (ref "C24") (pin "1") (pinfunction "1_1") (pintype "passive"))
      (node (ref "C25") (pin "1") (pinfunction "1_1") (pintype "passive"))
      (node (ref "C26") (pin "1") (pinfunction "1_1") (pintype "passive"))
      (node (ref "C27") (pin "1") (pinfunction "1_1") (pintype "passive"))
      (node (ref "C28") (pin "1") (pinfunction "1_1") (pintype "passive"))
      (node (ref "C29") (pin "1") (pinfunction "1_1") (pintype "passive"))
      (node (ref "C30") (pin "1") (pinfunction "1_1") (pintype "passive"))
      (node (ref "C31") (pin "1") (pinfunction "1_1") (pintype "passive"))
      (node (ref "C32") (pin "1") (pinfunction "1_1") (pintype "passive"))
      (node (ref "C33") (pin "1") (pinfunction "1_1") (pintype "passive"))
      (node (ref "C34") (pin "1") (pinfunction "1_1") (pintype "passive"))
      (node (ref "D1") (pin "2") (pinfunction "A2_2") (pintype "passive"))
      (node (ref "FB4") (pin "2") (pinfunction "2_2") (pintype "passive"))
      (node (ref "L1") (pin "1") (pinfunction "1_1") (pintype "passive"))
      (node (ref "U1") (pin "108") (pinfunction "VDD_108") (pintype "power_in"))
      (node (ref "U1") (pin "121") (pinfunction "VDD_121") (pintype "power_in"))
      (node (ref "U1") (pin "131") (pinfunction "VDD_131") (pintype "power_in"))
      (node (ref "U1") (pin "144") (pinfunction "VDD_144") (pintype "power_in"))
      (node (ref "U1") (pin "17") (pinfunction "VDD_17") (pintype "power_in"))
      (node (ref "U1") (pin "30") (pinfunction "VDD_30") (pintype "power_in"))
      (node (ref "U1") (pin "39") (pinfunction "VDD_39") (pintype "power_in"))
      (node (ref "U1") (pin "52") (pinfunction "VDD_52") (pintype "power_in"))
      (node (ref "U1") (pin "62") (pinfunction "VDD_62") (pintype "power_in"))
      (node (ref "U1") (pin "72") (pinfunction "VDD_72") (pintype "power_in"))
      (node (ref "U1") (pin "84") (pinfunction "VDD_84") (pintype "power_in"))
      (node (ref "U1") (pin "95") (pinfunction "VDD_95") (pintype "power_in"))
    )
    (net (code "91") (name "MCU_A3V3") (class "Default")
      (node (ref "C12") (pin "1") (pinfunction "1_1") (pintype "passive"))
      (node (ref "C13") (pin "1") (pinfunction "1_1") (pintype "passive"))
      (node (ref "FB1") (pin "1") (pinfunction "1_1") (pintype "passive"))
      (node (ref "L1") (pin "2") (pinfunction "2_2") (pintype "passive"))
      (node (ref "U1") (pin "33") (pinfunction "VDDA_33") (pintype "power_in"))
    )
    (net (code "92") (name "MCU_AGND") (class "Default")
      (node (ref "C12") (pin "2") (pinfunction "2_2") (pintype "passive"))
      (node (ref "C13") (pin "2") (pinfunction "2_2") (pintype "passive"))
      (node (ref "C3") (pin "2") (pinfunction "2_2") (pintype "passive"))
      (node (ref "C4") (pin "2") (pinfunction "2_2") (pintype "passive"))
      (node (ref "FB2") (pin "1") (pinfunction "1_1") (pintype "passive"))
      (node (ref "FB2") (pin "2") (pinfunction "2_2") (pintype "passive"))
      (node (ref "FB3") (pin "2") (pinfunction "2_2") (pintype "passive"))
      (node (ref "U1") (pin "31") (pinfunction "VSSA_31") (pintype "power_in"))
    )
    (net (code "93") (name "MCU_Aref") (class "Default")
      (node (ref "C3") (pin "1") (pinfunction "1_1") (pintype "passive"))
      (node (ref "C4") (pin "1") (pinfunction "1_1") (pintype "passive"))
      (node (ref "FB1") (pin "2") (pinfunction "2_2") (pintype "passive"))
      (node (ref "U1") (pin "32") (pinfunction "VREF+_32") (pintype "power_in"))
    )
    (net (code "94") (name "MCU_VBAT") (class "Default")
      (node (ref "C10") (pin "1") (pinfunction "1_1") (pintype "passive"))
      (node (ref "C8") (pin "1") (pinfunction "1_1") (pintype "passive"))
      (node (ref "D1") (pin "3") (pinfunction "K_3") (pintype "passive"))
      (node (ref "U1") (pin "6") (pinfunction "VBAT_6") (pintype "power_in"))
    )
    (net (code "95") (name "Net-(BT1-+)") (class "Default")
      (node (ref "BT1") (pin "1") (pinfunction "+_1") (pintype "passive"))
      (node (ref "D1") (pin "1") (pinfunction "A1_1") (pintype "passive"))
    )
    (net (code "96") (name "Net-(C7-Pad1)") (class "Default")
      (node (ref "C7") (pin "1") (pinfunction "1_1") (pintype "passive"))
      (node (ref "R2") (pin "1") (pinfunction "1_1") (pintype "passive"))
    )
    (net (code "97") (name "Net-(U1B-BOOT0)") (class "Default")
      (node (ref "R1") (pin "2") (pinfunction "2_2") (pintype "passive"))
      (node (ref "U1") (pin "138") (pinfunction "BOOT0_138") (pintype "input"))
    )
    (net (code "98") (name "Net-(U1B-VCAP_1)") (class "Default")
      (node (ref "C1") (pin "1") (pinfunction "1_1") (pintype "passive"))
      (node (ref "U1") (pin "71") (pinfunction "VCAP_1_71") (pintype "power_in"))
    )
    (net (code "99") (name "Net-(U1B-VCAP_2)") (class "Default")
      (node (ref "C2") (pin "1") (pinfunction "1_1") (pintype "passive"))
      (node (ref "U1") (pin "106") (pinfunction "VCAP_2_106") (pintype "power_in"))
    )
    (net (code "100") (name "unconnected-(U1A-PA15(JTDI)-Pad110)") (class "Default")
      (node (ref "U1") (pin "110") (pinfunction "PA15(JTDI)_110") (pintype "bidirectional"))
    )
    (net (code "101") (name "unconnected-(U1A-PB2-BOOT1(PB2)-Pad48)") (class "Default")
      (node (ref "U1") (pin "48") (pinfunction "PB2-BOOT1(PB2)_48") (pintype "bidirectional"))
    )
    (net (code "102") (name "unconnected-(U1A-PB3(JTDO{slash}TRACESWO)-Pad133)") (class "Default")
      (node (ref "U1") (pin "133") (pinfunction "PB3(JTDO/TRACESWO)_133") (pintype "bidirectional"))
    )
    (net (code "103") (name "unconnected-(U1A-PB5-Pad135)") (class "Default")
      (node (ref "U1") (pin "135") (pinfunction "PB5_135") (pintype "bidirectional"))
    )
    (net (code "104") (name "unconnected-(U1A-PC8-Pad98)") (class "Default")
      (node (ref "U1") (pin "98") (pinfunction "PC8_98") (pintype "bidirectional"))
    )
    (net (code "105") (name "unconnected-(U1A-PC9-Pad99)") (class "Default")
      (node (ref "U1") (pin "99") (pinfunction "PC9_99") (pintype "bidirectional"))
    )
    (net (code "106") (name "unconnected-(U1A-PC10-Pad111)") (class "Default")
      (node (ref "U1") (pin "111") (pinfunction "PC10_111") (pintype "bidirectional"))
    )
    (net (code "107") (name "unconnected-(U1A-PC11-Pad112)") (class "Default")
      (node (ref "U1") (pin "112") (pinfunction "PC11_112") (pintype "bidirectional"))
    )
    (net (code "108") (name "unconnected-(U1A-PC12-Pad113)") (class "Default")
      (node (ref "U1") (pin "113") (pinfunction "PC12_113") (pintype "bidirectional"))
    )
    (net (code "109") (name "unconnected-(U1A-PC13-Pad7)") (class "Default")
      (node (ref "U1") (pin "7") (pinfunction "PC13_7") (pintype "bidirectional"))
    )
    (net (code "110") (name "unconnected-(U1A-PD2-Pad116)") (class "Default")
      (node (ref "U1") (pin "116") (pinfunction "PD2_116") (pintype "bidirectional"))
    )
    (net (code "111") (name "unconnected-(U1A-PD4-Pad118)") (class "Default")
      (node (ref "U1") (pin "118") (pinfunction "PD4_118") (pintype "bidirectional"))
    )
    (net (code "112") (name "unconnected-(U1A-PD7-Pad123)") (class "Default")
      (node (ref "U1") (pin "123") (pinfunction "PD7_123") (pintype "bidirectional"))
    )
    (net (code "113") (name "unconnected-(U1A-PD13-Pad82)") (class "Default")
      (node (ref "U1") (pin "82") (pinfunction "PD13_82") (pintype "bidirectional"))
    )
    (net (code "114") (name "unconnected-(U1B-PDR_ON-Pad143)") (class "Default")
      (node (ref "U1") (pin "143") (pinfunction "PDR_ON_143") (pintype "input+no_connect"))
    )
    (net (code "115") (name "unconnected-(U1B-PE2-Pad1)") (class "Default")
      (node (ref "U1") (pin "1") (pinfunction "PE2_1") (pintype "bidirectional"))
    )
    (net (code "116") (name "unconnected-(U1B-PE3-Pad2)") (class "Default")
      (node (ref "U1") (pin "2") (pinfunction "PE3_2") (pintype "bidirectional"))
    )
    (net (code "117") (name "unconnected-(U1B-PE4-Pad3)") (class "Default")
      (node (ref "U1") (pin "3") (pinfunction "PE4_3") (pintype "bidirectional"))
    )
    (net (code "118") (name "unconnected-(U1B-PE5-Pad4)") (class "Default")
      (node (ref "U1") (pin "4") (pinfunction "PE5_4") (pintype "bidirectional"))
    )
    (net (code "119") (name "unconnected-(U1B-PE6-Pad5)") (class "Default")
      (node (ref "U1") (pin "5") (pinfunction "PE6_5") (pintype "bidirectional"))
    )
    (net (code "120") (name "unconnected-(U1B-PF6-Pad18)") (class "Default")
      (node (ref "U1") (pin "18") (pinfunction "PF6_18") (pintype "bidirectional"))
    )
    (net (code "121") (name "unconnected-(U1B-PF7-Pad19)") (class "Default")
      (node (ref "U1") (pin "19") (pinfunction "PF7_19") (pintype "bidirectional"))
    )
    (net (code "122") (name "unconnected-(U1B-PF8-Pad20)") (class "Default")
      (node (ref "U1") (pin "20") (pinfunction "PF8_20") (pintype "bidirectional"))
    )
    (net (code "123") (name "unconnected-(U1B-PF9-Pad21)") (class "Default")
      (node (ref "U1") (pin "21") (pinfunction "PF9_21") (pintype "bidirectional"))
    )
    (net (code "124") (name "unconnected-(U1B-PG3-Pad88)") (class "Default")
      (node (ref "U1") (pin "88") (pinfunction "PG3_88") (pintype "bidirectional"))
    )
    (net (code "125") (name "unconnected-(U1B-PG9-Pad124)") (class "Default")
      (node (ref "U1") (pin "124") (pinfunction "PG9_124") (pintype "bidirectional"))
    )
    (net (code "126") (name "unconnected-(U1B-PG13-Pad128)") (class "Default")
      (node (ref "U1") (pin "128") (pinfunction "PG13_128") (pintype "bidirectional"))
    )
    (net (code "127") (name "unconnected-(U1B-PG14-Pad129)") (class "Default")
      (node (ref "U1") (pin "129") (pinfunction "PG14_129") (pintype "bidirectional"))
    )
  )
)
